# rx_path_lp_filter.net
KiCad netlist of a schematic drawn in Altium Designer
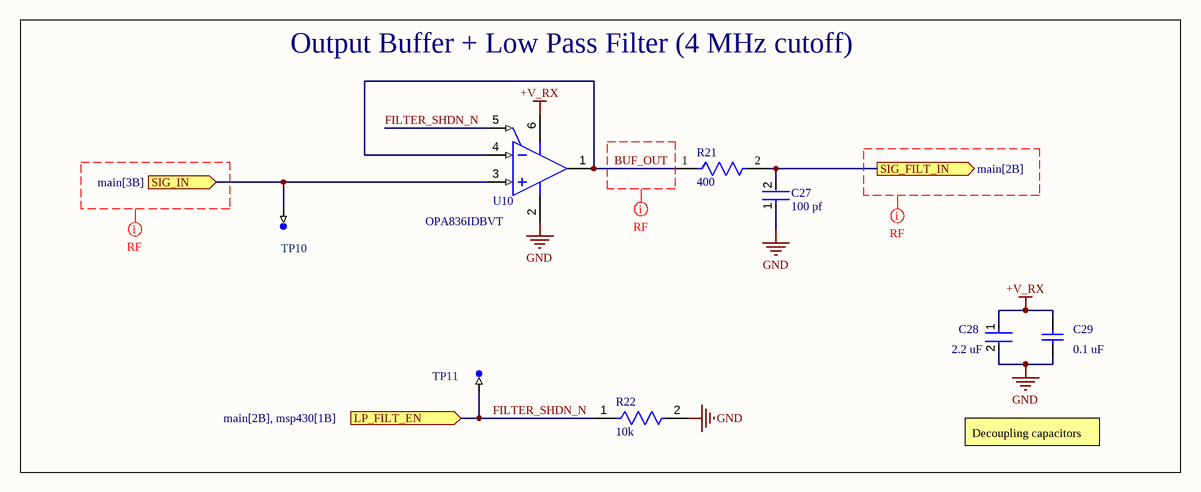
[diagram p0: rx_path_lp_filter.SchDoc]

(export (version "E")
  (design (tool "Eeschema 10.0.6"))
  (components
    (comp (ref "C27")
      (value "100 pf")
      (footprint "FP-0402-L_1_0_1-W_0_5_0_1-MFG")
      (description "04025A101FAT2A")
      (fields (field (name "VOLTAGE") "50V") (field (name "TOLERANCE") "1%"))
      (libsource (lib "Altium Content Vault") (part "b4654b650e69147ec39a6b967a45e02"))
    )
    (comp (ref "C28")
      (value "2.2 uF")
      (footprint "FP-C1005-050-0_15-0_1-MFG")
      (description "C1005X7S1A225K050BC")
      (fields (field (name "TOLERANCE") "10%"))
      (libsource (lib "Altium Content Vault") (part "b4654b650e69147ec39a6b967a45e02"))
    )
    (comp (ref "C29")
      (value "0.1 uF")
      (footprint "CAPC1005X55X30LL05T10")
      (description "C0402C104K4RACTU")
      (fields (field (name "MANUFACTURER") "Kemet"))
      (libsource (lib "Altium Content Vault") (part "CAP"))
    )
    (comp (ref "R21")
      (value "400")
      (footprint "FP-CRCW0402-C-e3-MFG")
      (description "CRCW04021R00FKEDC")
      (fields (field (name "TOLERANCE") "1%"))
      (libsource (lib "Altium Content Vault") (part "1029c3af85768c4190bb7ad29bc67b5"))
    )
    (comp (ref "R22")
      (value "10k")
      (footprint "FP-CRCW0402-e3-IPC_B")
      (description "CRCW040210K0JNED")
      (fields (field (name "TOLERANCE") "5%"))
      (libsource (lib "Altium Content Vault") (part "1029c3af85768c4190bb7ad29bc67b5"))
    )
    (comp (ref "TP10")
      (value "TP-SM-C-100")
      (footprint "TP-SM-C-100")
      (description "Test Point, Surface Mount, Circular, Pad Diameter 1 mm")
      (libsource (lib "wulpus") (part "CMP-0484-00002-1"))
    )
    (comp (ref "TP11")
      (value "TP-SM-C-100")
      (footprint "TP-SM-C-100")
      (description "Test Point, Surface Mount, Circular, Pad Diameter 1 mm")
      (libsource (lib "wulpus") (part "CMP-0484-00002-1"))
    )
    (comp (ref "U10")
      (value "OPA836IDBVT")
      (footprint "DBV0006A_L")
      (fields (field (name "MANUFACTURER") "Texas Instruments"))
      (libsource (lib "wulpus") (part "CMP-0018-00480-2"))
    )
  )
  (nets
    (net (code "1") (name "+V_RX") (class "Default")
      (node (ref "C28") (pin "1") (pinfunction "1_1") (pintype "passive"))
      (node (ref "C29") (pin "2") (pinfunction "2_2") (pintype "passive"))
      (node (ref "U10") (pin "6") (pinfunction "VS+_6") (pintype "power_in"))
    )
    (net (code "2") (name "/BUF_OUT") (class "Default")
      (node (ref "R21") (pin "1") (pinfunction "1_1") (pintype "passive"))
      (node (ref "U10") (pin "1") (pinfunction "VOUT_1") (pintype "tri_state"))
      (node (ref "U10") (pin "4") (pinfunction "VIN-_4") (pintype "input"))
    )
    (net (code "3") (name "/FILTER_SHDN_N") (class "Default")
      (node (ref "R22") (pin "1") (pinfunction "1_1") (pintype "passive"))
      (node (ref "TP11") (pin "1") (pinfunction "1_1") (pintype "input"))
      (node (ref "U10") (pin "5") (pinfunction "~{PD}_5") (pintype "input"))
    )
    (net (code "4") (name "/SIG_FILT_IN") (class "Default")
      (node (ref "C27") (pin "2") (pinfunction "2_2") (pintype "passive"))
      (node (ref "R21") (pin "2") (pinfunction "2_2") (pintype "passive"))
    )
    (net (code "5") (name "/SIG_IN") (class "Default")
      (node (ref "TP10") (pin "1") (pinfunction "1_1") (pintype "input"))
      (node (ref "U10") (pin "3") (pinfunction "VIN+_3") (pintype "input"))
    )
    (net (code "6") (name "GND") (class "Default")
      (node (ref "C27") (pin "1") (pinfunction "1_1") (pintype "passive"))
      (node (ref "C28") (pin "2") (pinfunction "2_2") (pintype "passive"))
      (node (ref "C29") (pin "1") (pinfunction "1_1") (pintype "passive"))
      (node (ref "R22") (pin "2") (pinfunction "2_2") (pintype "passive"))
      (node (ref "U10") (pin "2") (pinfunction "VS-_2") (pintype "power_in"))
    )
  )
)
